# mjholmes_RaspPiXBeeShield_v1.net
KiCad netlist of a schematic drawn in EAGLE
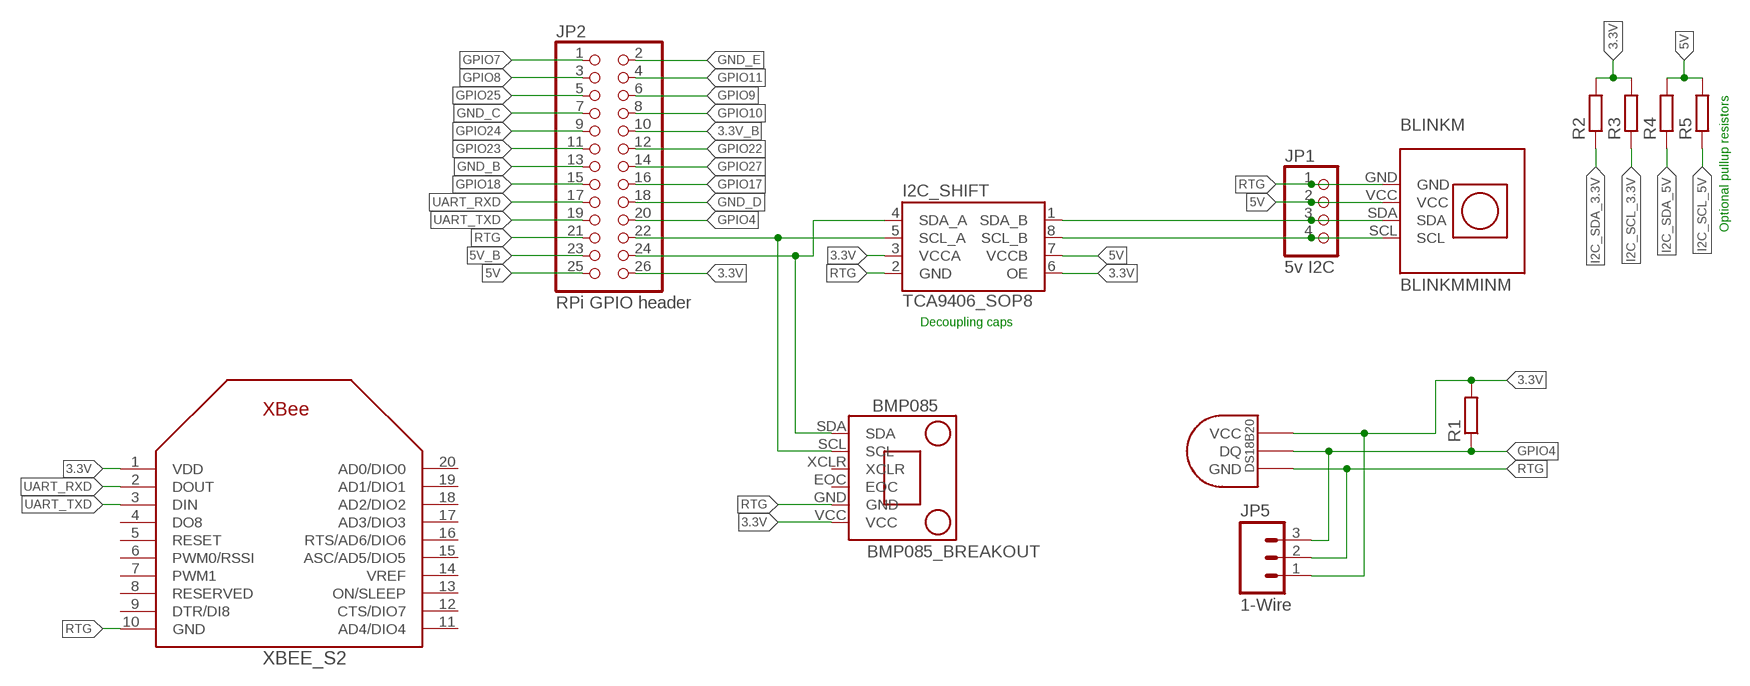
[diagram p0: schematic, sheet 1]

(export (version "E")
  (design (tool "Eeschema 10.0.6"))
  (components
    (comp (ref "BLINKM")
      (value "BLINKMMINM")
      (footprint "eagle-import:BLINKM_MINM")
      (libsource (lib "eagle-import") (part "BLINKMMINM"))
    )
    (comp (ref "BMP085")
      (value "BMP085_BREAKOUT")
      (footprint "eagle-import:BMP085_BREAKOUT")
      (libsource (lib "eagle-import") (part "BMP085_BREAKOUT"))
    )
    (comp (ref "I2C_SHIFT")
      (value "TCA9406_SOP8")
      (footprint "eagle-import:SOP8")
      (libsource (lib "eagle-import") (part "TCA9406_SOP8"))
    )
    (comp (ref "JP1")
      (value "5v I2C")
      (footprint "eagle-import:1X04")
      (libsource (lib "eagle-import") (part "PINHD-1X4"))
    )
    (comp (ref "JP2")
      (value "RPi GPIO header")
      (footprint "eagle-import:2X13")
      (libsource (lib "eagle-import") (part "PINHD-2X13"))
    )
    (comp (ref "JP5")
      (value "1-Wire")
      (footprint "eagle-import:JST-3-PTH")
      (libsource (lib "eagle-import") (part "M03JST-PTH"))
    )
    (comp (ref "R1")
      (value "R-EU_R0603")
      (footprint "eagle-import:R0603")
      (libsource (lib "eagle-import") (part "R-EU_R0603"))
    )
    (comp (ref "R2")
      (value "R-EU_R0603")
      (footprint "eagle-import:R0603")
      (libsource (lib "eagle-import") (part "R-EU_R0603"))
    )
    (comp (ref "R3")
      (value "R-EU_R0603")
      (footprint "eagle-import:R0603")
      (libsource (lib "eagle-import") (part "R-EU_R0603"))
    )
    (comp (ref "R4")
      (value "R-EU_R0603")
      (footprint "eagle-import:R0603")
      (libsource (lib "eagle-import") (part "R-EU_R0603"))
    )
    (comp (ref "R5")
      (value "R-EU_R0603")
      (footprint "eagle-import:R0603")
      (libsource (lib "eagle-import") (part "R-EU_R0603"))
    )
    (comp (ref "U$3")
      (value "DS1820SOIC")
      (footprint "eagle-import:DS18B20_SOIC")
      (libsource (lib "eagle-import") (part "DS1820SOIC"))
    )
    (comp (ref "XBEE_S2")
      (value "XBEE S2")
      (footprint "eagle-import:XBEE_S2")
      (libsource (lib "eagle-import") (part "XBEE_S2"))
    )
  )
  (nets
    (net (code "1") (name "3.3V") (class "Default")
      (node (ref "BMP085") (pin "VCC") (pinfunction "VCC_VCC") (pintype "power_in"))
      (node (ref "I2C_SHIFT") (pin "3") (pinfunction "VCCA_3") (pintype "power_in"))
      (node (ref "I2C_SHIFT") (pin "6") (pinfunction "OE_6") (pintype "input"))
      (node (ref "JP2") (pin "26") (pinfunction "26_26") (pintype "passive"))
      (node (ref "JP5") (pin "1") (pinfunction "1_1") (pintype "passive"))
      (node (ref "R1") (pin "2") (pinfunction "2_2") (pintype "passive"))
      (node (ref "R2") (pin "2") (pinfunction "2_2") (pintype "passive"))
      (node (ref "R3") (pin "2") (pinfunction "2_2") (pintype "passive"))
      (node (ref "U$3") (pin "VCC") (pinfunction "VCC_VCC") (pintype "power_in"))
      (node (ref "XBEE_S2") (pin "1") (pinfunction "VDD_1") (pintype "power_in"))
    )
    (net (code "2") (name "3.3V_B") (class "Default")
      (node (ref "JP2") (pin "10") (pinfunction "10_10") (pintype "passive"))
    )
    (net (code "3") (name "5V") (class "Default")
      (node (ref "BLINKM") (pin "VCC") (pinfunction "VCC_VCC") (pintype "power_in"))
      (node (ref "I2C_SHIFT") (pin "7") (pinfunction "VCCB_7") (pintype "power_in"))
      (node (ref "JP1") (pin "2") (pinfunction "2_2") (pintype "passive"))
      (node (ref "JP2") (pin "25") (pinfunction "25_25") (pintype "passive"))
      (node (ref "R4") (pin "2") (pinfunction "2_2") (pintype "passive"))
      (node (ref "R5") (pin "2") (pinfunction "2_2") (pintype "passive"))
    )
    (net (code "4") (name "5V_B") (class "Default")
      (node (ref "JP2") (pin "23") (pinfunction "23_23") (pintype "passive"))
    )
    (net (code "5") (name "GND_B") (class "Default")
      (node (ref "JP2") (pin "13") (pinfunction "13_13") (pintype "passive"))
    )
    (net (code "6") (name "GND_C") (class "Default")
      (node (ref "JP2") (pin "7") (pinfunction "7_7") (pintype "passive"))
    )
    (net (code "7") (name "GND_D") (class "Default")
      (node (ref "JP2") (pin "18") (pinfunction "18_18") (pintype "passive"))
    )
    (net (code "8") (name "GND_E") (class "Default")
      (node (ref "JP2") (pin "2") (pinfunction "2_2") (pintype "passive"))
    )
    (net (code "9") (name "GPIO4") (class "Default")
      (node (ref "JP2") (pin "20") (pinfunction "20_20") (pintype "passive"))
      (node (ref "JP5") (pin "3") (pinfunction "3_3") (pintype "passive"))
      (node (ref "R1") (pin "1") (pinfunction "1_1") (pintype "passive"))
      (node (ref "U$3") (pin "DQ") (pinfunction "DQ_DQ") (pintype "bidirectional"))
    )
    (net (code "10") (name "GPIO7") (class "Default")
      (node (ref "JP2") (pin "1") (pinfunction "1_1") (pintype "passive"))
    )
    (net (code "11") (name "GPIO8") (class "Default")
      (node (ref "JP2") (pin "3") (pinfunction "3_3") (pintype "passive"))
    )
    (net (code "12") (name "GPIO9") (class "Default")
      (node (ref "JP2") (pin "6") (pinfunction "6_6") (pintype "passive"))
    )
    (net (code "13") (name "GPIO10") (class "Default")
      (node (ref "JP2") (pin "8") (pinfunction "8_8") (pintype "passive"))
    )
    (net (code "14") (name "GPIO11") (class "Default")
      (node (ref "JP2") (pin "4") (pinfunction "4_4") (pintype "passive"))
    )
    (net (code "15") (name "GPIO17") (class "Default")
      (node (ref "JP2") (pin "16") (pinfunction "16_16") (pintype "passive"))
    )
    (net (code "16") (name "GPIO18") (class "Default")
      (node (ref "JP2") (pin "15") (pinfunction "15_15") (pintype "passive"))
    )
    (net (code "17") (name "GPIO22") (class "Default")
      (node (ref "JP2") (pin "12") (pinfunction "12_12") (pintype "passive"))
    )
    (net (code "18") (name "GPIO23") (class "Default")
      (node (ref "JP2") (pin "11") (pinfunction "11_11") (pintype "passive"))
    )
    (net (code "19") (name "GPIO24") (class "Default")
      (node (ref "JP2") (pin "9") (pinfunction "9_9") (pintype "passive"))
    )
    (net (code "20") (name "GPIO25") (class "Default")
      (node (ref "JP2") (pin "5") (pinfunction "5_5") (pintype "passive"))
    )
    (net (code "21") (name "GPIO27") (class "Default")
      (node (ref "JP2") (pin "14") (pinfunction "14_14") (pintype "passive"))
    )
    (net (code "22") (name "I2C_SCL_3.3V") (class "Default")
      (node (ref "BMP085") (pin "SCL") (pinfunction "SCL_SCL") (pintype "bidirectional"))
      (node (ref "I2C_SHIFT") (pin "5") (pinfunction "SCL_A_5") (pintype "bidirectional"))
      (node (ref "JP2") (pin "22") (pinfunction "22_22") (pintype "passive"))
      (node (ref "R3") (pin "1") (pinfunction "1_1") (pintype "passive"))
    )
    (net (code "23") (name "I2C_SCL_5V") (class "Default")
      (node (ref "BLINKM") (pin "SCL") (pinfunction "SCL_SCL") (pintype "bidirectional"))
      (node (ref "I2C_SHIFT") (pin "8") (pinfunction "SCL_B_8") (pintype "bidirectional"))
      (node (ref "JP1") (pin "4") (pinfunction "4_4") (pintype "passive"))
      (node (ref "R5") (pin "1") (pinfunction "1_1") (pintype "passive"))
    )
    (net (code "24") (name "I2C_SDA_3.3V") (class "Default")
      (node (ref "BMP085") (pin "SDA") (pinfunction "SDA_SDA") (pintype "bidirectional"))
      (node (ref "I2C_SHIFT") (pin "4") (pinfunction "SDA_A_4") (pintype "bidirectional"))
      (node (ref "JP2") (pin "24") (pinfunction "24_24") (pintype "passive"))
      (node (ref "R2") (pin "1") (pinfunction "1_1") (pintype "passive"))
    )
    (net (code "25") (name "I2C_SDA_5V") (class "Default")
      (node (ref "BLINKM") (pin "SDA") (pinfunction "SDA_SDA") (pintype "bidirectional"))
      (node (ref "I2C_SHIFT") (pin "1") (pinfunction "SDA_B_1") (pintype "bidirectional"))
      (node (ref "JP1") (pin "3") (pinfunction "3_3") (pintype "passive"))
      (node (ref "R4") (pin "1") (pinfunction "1_1") (pintype "passive"))
    )
    (net (code "26") (name "RTG") (class "Default")
      (node (ref "BLINKM") (pin "GND") (pinfunction "GND_GND") (pintype "power_in"))
      (node (ref "BMP085") (pin "GND") (pinfunction "GND_GND") (pintype "power_in"))
      (node (ref "I2C_SHIFT") (pin "2") (pinfunction "GND_2") (pintype "power_in"))
      (node (ref "JP1") (pin "1") (pinfunction "1_1") (pintype "passive"))
      (node (ref "JP2") (pin "21") (pinfunction "21_21") (pintype "passive"))
      (node (ref "JP5") (pin "2") (pinfunction "2_2") (pintype "passive"))
      (node (ref "U$3") (pin "GND") (pinfunction "GND_GND") (pintype "power_in"))
      (node (ref "XBEE_S2") (pin "10") (pinfunction "GND_10") (pintype "power_in"))
    )
    (net (code "27") (name "UART_RXD") (class "Default")
      (node (ref "JP2") (pin "17") (pinfunction "17_17") (pintype "passive"))
      (node (ref "XBEE_S2") (pin "2") (pinfunction "DOUT_2") (pintype "output"))
    )
    (net (code "28") (name "UART_TXD") (class "Default")
      (node (ref "JP2") (pin "19") (pinfunction "19_19") (pintype "passive"))
      (node (ref "XBEE_S2") (pin "3") (pinfunction "DIN_3") (pintype "input"))
    )
    (net (code "29") (name "unconnected-(BMP085-PadEOC)") (class "Default")
      (node (ref "BMP085") (pin "EOC") (pinfunction "EOC_EOC") (pintype "output"))
    )
    (net (code "30") (name "unconnected-(BMP085-PadXCLR)") (class "Default")
      (node (ref "BMP085") (pin "XCLR") (pinfunction "XCLR_XCLR") (pintype "input"))
    )
    (net (code "31") (name "unconnected-(XBEE_S2-AD0{slash}DIO0-Pad20)") (class "Default")
      (node (ref "XBEE_S2") (pin "20") (pinfunction "AD0/DIO0_20") (pintype "bidirectional"))
    )
    (net (code "32") (name "unconnected-(XBEE_S2-AD1{slash}DIO1-Pad19)") (class "Default")
      (node (ref "XBEE_S2") (pin "19") (pinfunction "AD1/DIO1_19") (pintype "bidirectional"))
    )
    (net (code "33") (name "unconnected-(XBEE_S2-AD2{slash}DIO2-Pad18)") (class "Default")
      (node (ref "XBEE_S2") (pin "18") (pinfunction "AD2/DIO2_18") (pintype "bidirectional"))
    )
    (net (code "34") (name "unconnected-(XBEE_S2-AD3{slash}DIO3-Pad17)") (class "Default")
      (node (ref "XBEE_S2") (pin "17") (pinfunction "AD3/DIO3_17") (pintype "bidirectional"))
    )
    (net (code "35") (name "unconnected-(XBEE_S2-AD4{slash}DIO4-Pad11)") (class "Default")
      (node (ref "XBEE_S2") (pin "11") (pinfunction "AD4/DIO4_11") (pintype "bidirectional"))
    )
    (net (code "36") (name "unconnected-(XBEE_S2-ASC{slash}AD5{slash}DIO5-Pad15)") (class "Default")
      (node (ref "XBEE_S2") (pin "15") (pinfunction "ASC/AD5/DIO5_15") (pintype "bidirectional"))
    )
    (net (code "37") (name "unconnected-(XBEE_S2-CTS{slash}DIO7-Pad12)") (class "Default")
      (node (ref "XBEE_S2") (pin "12") (pinfunction "CTS/DIO7_12") (pintype "bidirectional"))
    )
    (net (code "38") (name "unconnected-(XBEE_S2-DO8-Pad4)") (class "Default")
      (node (ref "XBEE_S2") (pin "4") (pinfunction "DO8_4") (pintype "output"))
    )
    (net (code "39") (name "unconnected-(XBEE_S2-DTR{slash}DI8-Pad9)") (class "Default")
      (node (ref "XBEE_S2") (pin "9") (pinfunction "DTR/DI8_9") (pintype "input"))
    )
    (net (code "40") (name "unconnected-(XBEE_S2-ON{slash}SLEEP-Pad13)") (class "Default")
      (node (ref "XBEE_S2") (pin "13") (pinfunction "ON/SLEEP_13") (pintype "output"))
    )
    (net (code "41") (name "unconnected-(XBEE_S2-PWM0{slash}RSSI-Pad6)") (class "Default")
      (node (ref "XBEE_S2") (pin "6") (pinfunction "PWM0/RSSI_6") (pintype "output"))
    )
    (net (code "42") (name "unconnected-(XBEE_S2-PWM1-Pad7)") (class "Default")
      (node (ref "XBEE_S2") (pin "7") (pinfunction "PWM1_7") (pintype "output"))
    )
    (net (code "43") (name "unconnected-(XBEE_S2-RESERVED-Pad8)") (class "Default")
      (node (ref "XBEE_S2") (pin "8") (pinfunction "RESERVED_8") (pintype "no_connect"))
    )
    (net (code "44") (name "unconnected-(XBEE_S2-RESET-Pad5)") (class "Default")
      (node (ref "XBEE_S2") (pin "5") (pinfunction "RESET_5") (pintype "input"))
    )
    (net (code "45") (name "unconnected-(XBEE_S2-RTS{slash}AD6{slash}DIO6-Pad16)") (class "Default")
      (node (ref "XBEE_S2") (pin "16") (pinfunction "RTS/AD6/DIO6_16") (pintype "bidirectional"))
    )
    (net (code "46") (name "unconnected-(XBEE_S2-VREF-Pad14)") (class "Default")
      (node (ref "XBEE_S2") (pin "14") (pinfunction "VREF_14") (pintype "input"))
    )
  )
)
